# USB_Serial_Quad.net
KiCad netlist of a schematic drawn in Altium Designer
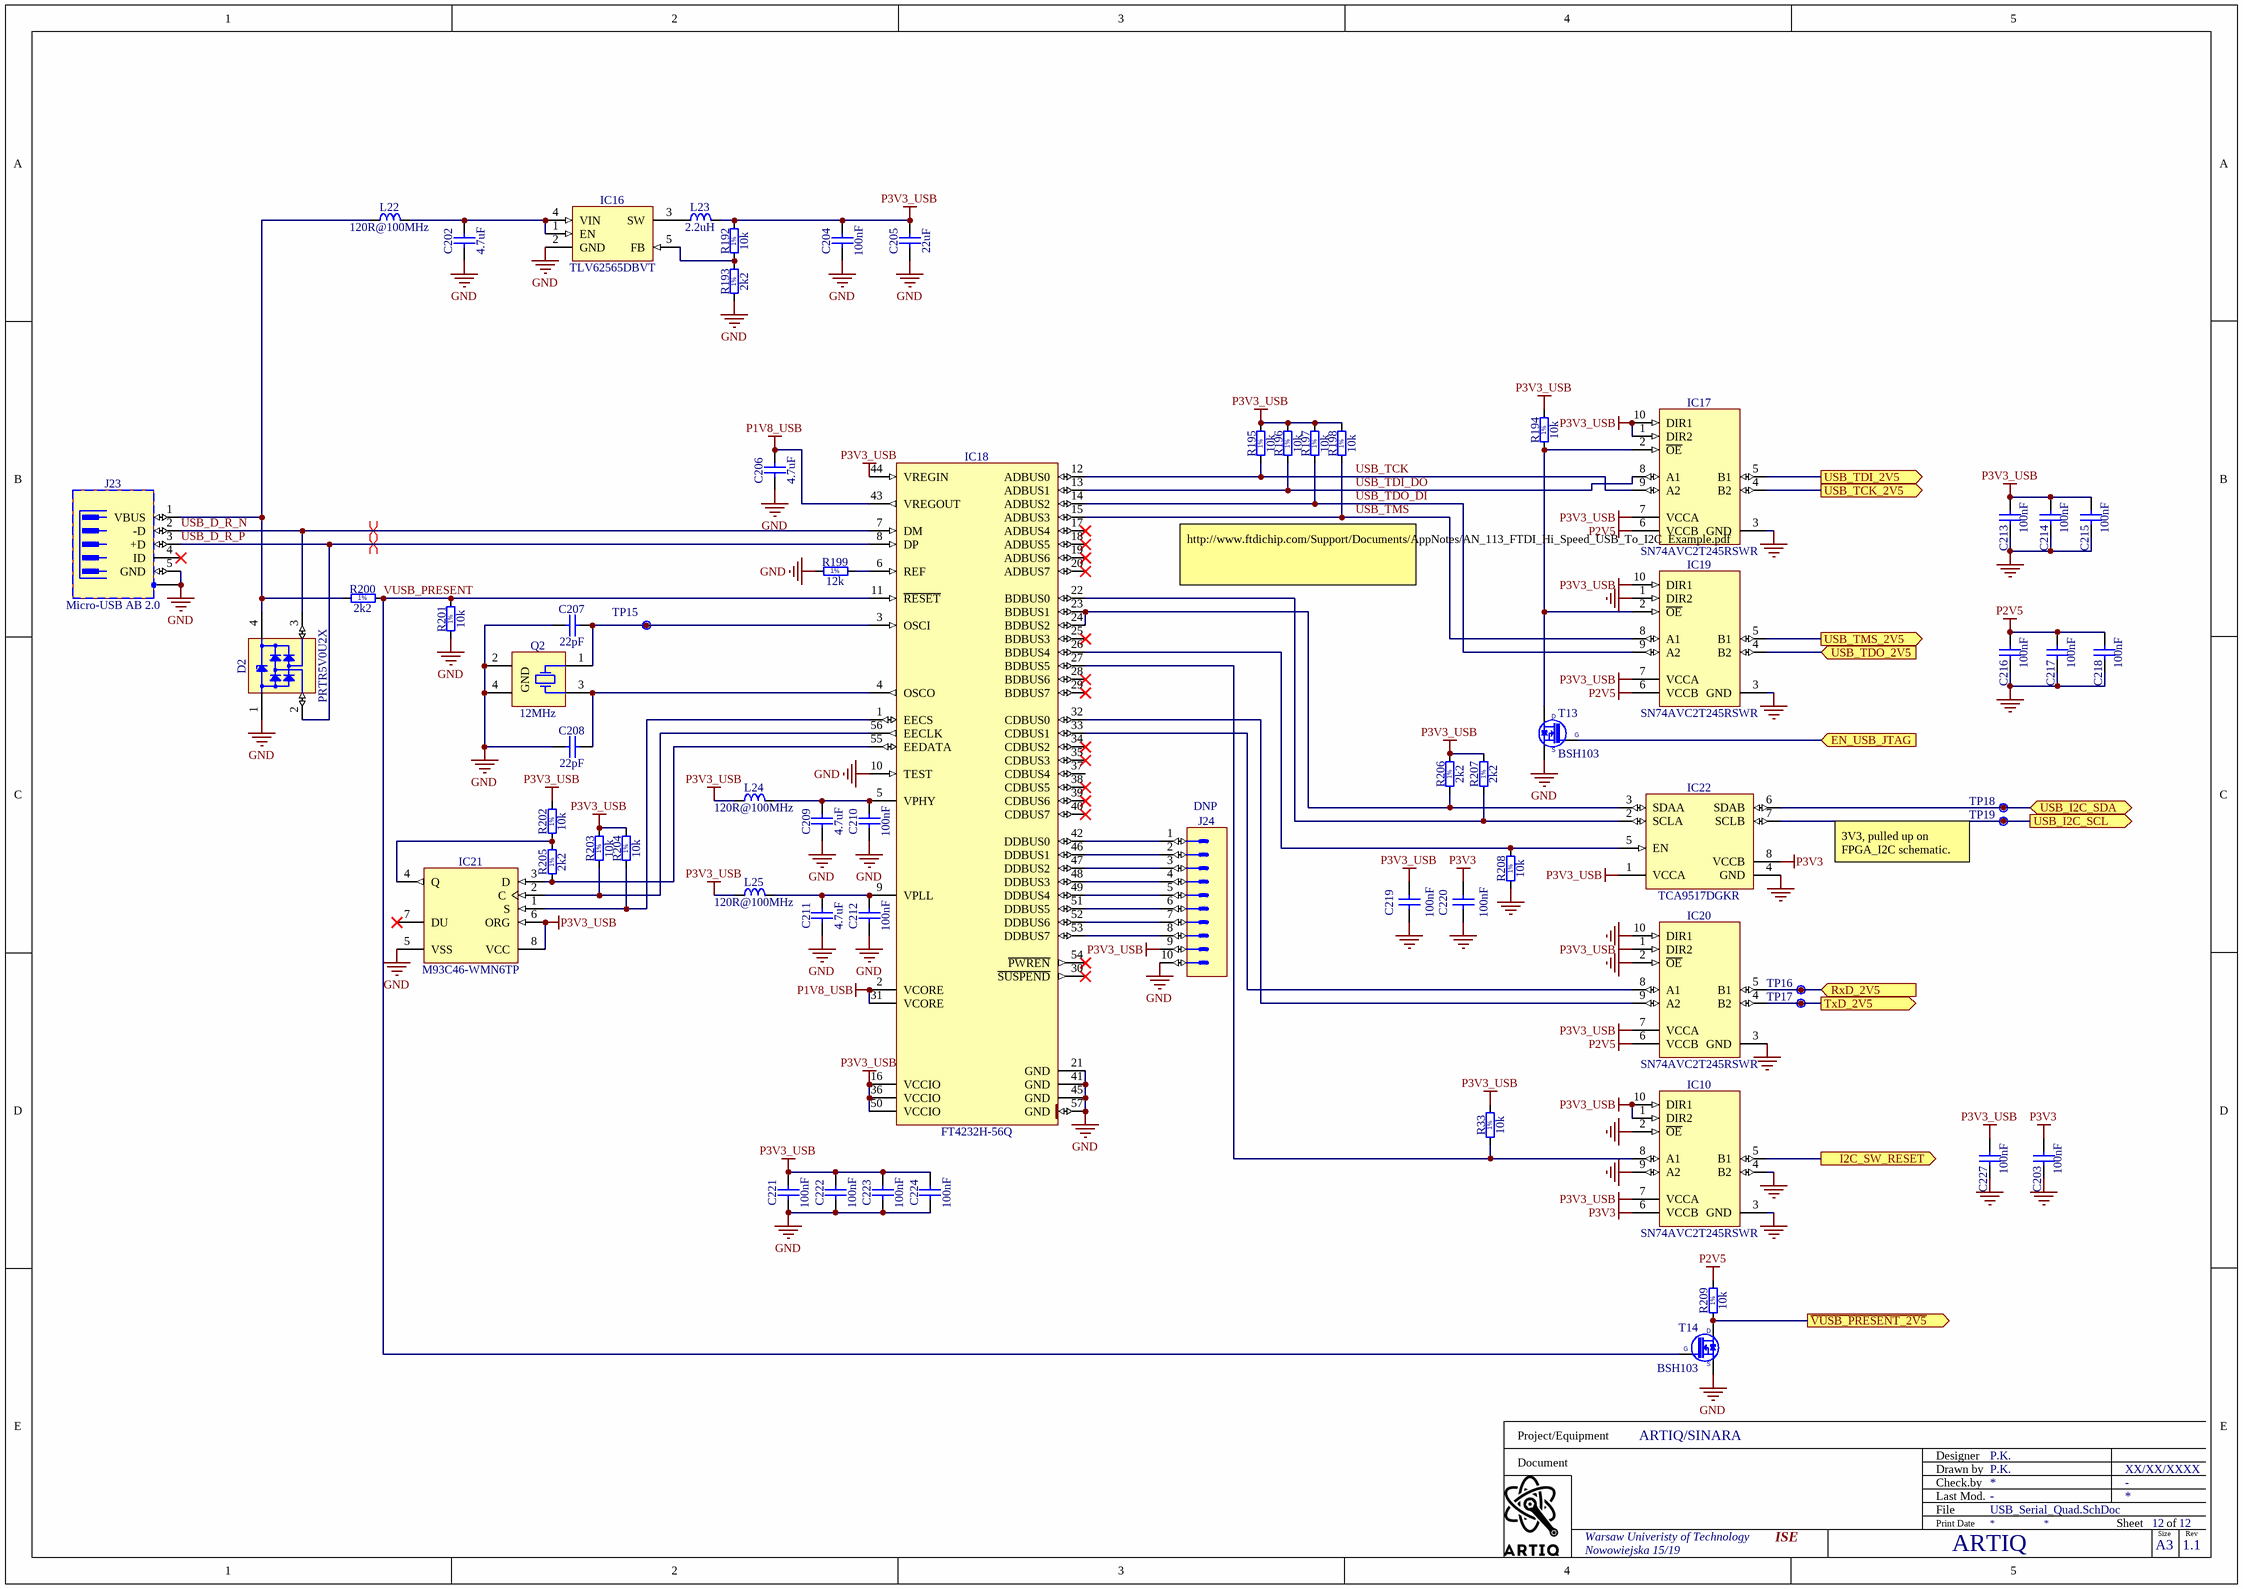
[diagram p0: USB_Serial_Quad.SchDoc]

(export (version "E")
  (design (tool "Eeschema 10.0.6"))
  (components
    (comp (ref "C202")
      (value "4.7uF")
      (footprint "CAPC2012X135N")
      (description "Non-polarised capacitor")
      (fields
        (field (name "PART NUMBER") "CC0805_4.7UF_10V_10%_X5R")
        (field (name "VOLTAGE") "10V")
        (field (name "AUTHOR") "CERN DEM JLC")
      )
      (libsource (lib "Capacitors") (part "Capacitor - non polarized"))
    )
    (comp (ref "C203")
      (value "100nF")
      (footprint "CAPC0603X33N")
      (description "Non-polarised capacitor")
      (fields
        (field (name "PART NUMBER") "CC0201_100NF_6.3V_10%_X5R")
        (field (name "VOLTAGE") "6.3V")
        (field (name "AUTHOR") "CERN DEM JLC")
      )
      (libsource (lib "Capacitors") (part "Capacitor - non polarized"))
    )
    (comp (ref "C204")
      (value "100nF")
      (footprint "CAPC0603X33N")
      (description "Non-polarised capacitor")
      (fields
        (field (name "PART NUMBER") "CC0201_100NF_6.3V_10%_X5R")
        (field (name "VOLTAGE") "6.3V")
        (field (name "AUTHOR") "CERN DEM JLC")
      )
      (libsource (lib "Capacitors") (part "Capacitor - non polarized"))
    )
    (comp (ref "C205")
      (value "22uF")
      (footprint "CAPC1709X100N")
      (description "Non-polarised capacitor")
      (fields
        (field (name "PART NUMBER") "CC0603_22UF_6.3V_20%_X5R")
        (field (name "VOLTAGE") "6.3V")
        (field (name "AUTHOR") "CERN DEM JLC")
      )
      (libsource (lib "Capacitors") (part "Capacitor - non polarized"))
    )
    (comp (ref "C206")
      (value "4.7uF")
      (footprint "CAPC2012X135N")
      (description "Non-polarised capacitor")
      (fields
        (field (name "PART NUMBER") "CC0805_4.7UF_10V_10%_X5R")
        (field (name "VOLTAGE") "10V")
        (field (name "AUTHOR") "CERN DEM JLC")
      )
      (libsource (lib "Capacitors") (part "Capacitor - non polarized"))
    )
    (comp (ref "C207")
      (value "22pF")
      (footprint "CAPC1005X55N")
      (description "Non-polarised capacitor")
      (fields
        (field (name "PART NUMBER") "CC0402_22PF_50V_5%_C0G")
        (field (name "VOLTAGE") "50V")
        (field (name "AUTHOR") "CERN DEM JLC")
      )
      (libsource (lib "Capacitors") (part "Capacitor - non polarized"))
    )
    (comp (ref "C208")
      (value "22pF")
      (footprint "CAPC1005X55N")
      (description "Non-polarised capacitor")
      (fields
        (field (name "PART NUMBER") "CC0402_22PF_50V_5%_C0G")
        (field (name "VOLTAGE") "50V")
        (field (name "AUTHOR") "CERN DEM JLC")
      )
      (libsource (lib "Capacitors") (part "Capacitor - non polarized"))
    )
    (comp (ref "C209")
      (value "4.7uF")
      (footprint "CAPC2012X135N")
      (description "Non-polarised capacitor")
      (fields
        (field (name "PART NUMBER") "CC0805_4.7UF_10V_10%_X5R")
        (field (name "VOLTAGE") "10V")
        (field (name "AUTHOR") "CERN DEM JLC")
      )
      (libsource (lib "Capacitors") (part "Capacitor - non polarized"))
    )
    (comp (ref "C210")
      (value "100nF")
      (footprint "CAPC0603X33N")
      (description "Non-polarised capacitor")
      (fields
        (field (name "PART NUMBER") "CC0201_100NF_6.3V_10%_X5R")
        (field (name "VOLTAGE") "6.3V")
        (field (name "AUTHOR") "CERN DEM JLC")
      )
      (libsource (lib "Capacitors") (part "Capacitor - non polarized"))
    )
    (comp (ref "C211")
      (value "4.7uF")
      (footprint "CAPC2012X135N")
      (description "Non-polarised capacitor")
      (fields
        (field (name "PART NUMBER") "CC0805_4.7UF_10V_10%_X5R")
        (field (name "VOLTAGE") "10V")
        (field (name "AUTHOR") "CERN DEM JLC")
      )
      (libsource (lib "Capacitors") (part "Capacitor - non polarized"))
    )
    (comp (ref "C212")
      (value "100nF")
      (footprint "CAPC0603X33N")
      (description "Non-polarised capacitor")
      (fields
        (field (name "PART NUMBER") "CC0201_100NF_6.3V_10%_X5R")
        (field (name "VOLTAGE") "6.3V")
        (field (name "AUTHOR") "CERN DEM JLC")
      )
      (libsource (lib "Capacitors") (part "Capacitor - non polarized"))
    )
    (comp (ref "C213")
      (value "100nF")
      (footprint "CAPC0603X33N")
      (description "Non-polarised capacitor")
      (fields
        (field (name "PART NUMBER") "CC0201_100NF_6.3V_10%_X5R")
        (field (name "VOLTAGE") "6.3V")
        (field (name "AUTHOR") "CERN DEM JLC")
      )
      (libsource (lib "Capacitors") (part "Capacitor - non polarized"))
    )
    (comp (ref "C214")
      (value "100nF")
      (footprint "CAPC0603X33N")
      (description "Non-polarised capacitor")
      (fields
        (field (name "PART NUMBER") "CC0201_100NF_6.3V_10%_X5R")
        (field (name "VOLTAGE") "6.3V")
        (field (name "AUTHOR") "CERN DEM JLC")
      )
      (libsource (lib "Capacitors") (part "Capacitor - non polarized"))
    )
    (comp (ref "C215")
      (value "100nF")
      (footprint "CAPC0603X33N")
      (description "Non-polarised capacitor")
      (fields
        (field (name "PART NUMBER") "CC0201_100NF_6.3V_10%_X5R")
        (field (name "VOLTAGE") "6.3V")
        (field (name "AUTHOR") "CERN DEM JLC")
      )
      (libsource (lib "Capacitors") (part "Capacitor - non polarized"))
    )
    (comp (ref "C216")
      (value "100nF")
      (footprint "CAPC0603X33N")
      (description "Non-polarised capacitor")
      (fields
        (field (name "PART NUMBER") "CC0201_100NF_6.3V_10%_X5R")
        (field (name "VOLTAGE") "6.3V")
        (field (name "AUTHOR") "CERN DEM JLC")
      )
      (libsource (lib "Capacitors") (part "Capacitor - non polarized"))
    )
    (comp (ref "C217")
      (value "100nF")
      (footprint "CAPC0603X33N")
      (description "Non-polarised capacitor")
      (fields
        (field (name "PART NUMBER") "CC0201_100NF_6.3V_10%_X5R")
        (field (name "VOLTAGE") "6.3V")
        (field (name "AUTHOR") "CERN DEM JLC")
      )
      (libsource (lib "Capacitors") (part "Capacitor - non polarized"))
    )
    (comp (ref "C218")
      (value "100nF")
      (footprint "CAPC0603X33N")
      (description "Non-polarised capacitor")
      (fields
        (field (name "PART NUMBER") "CC0201_100NF_6.3V_10%_X5R")
        (field (name "VOLTAGE") "6.3V")
        (field (name "AUTHOR") "CERN DEM JLC")
      )
      (libsource (lib "Capacitors") (part "Capacitor - non polarized"))
    )
    (comp (ref "C219")
      (value "100nF")
      (footprint "CAPC0603X33N")
      (description "Non-polarised capacitor")
      (fields
        (field (name "PART NUMBER") "CC0201_100NF_6.3V_10%_X5R")
        (field (name "VOLTAGE") "6.3V")
        (field (name "AUTHOR") "CERN DEM JLC")
      )
      (libsource (lib "Capacitors") (part "Capacitor - non polarized"))
    )
    (comp (ref "C220")
      (value "100nF")
      (footprint "CAPC0603X33N")
      (description "Non-polarised capacitor")
      (fields
        (field (name "PART NUMBER") "CC0201_100NF_6.3V_10%_X5R")
        (field (name "VOLTAGE") "6.3V")
        (field (name "AUTHOR") "CERN DEM JLC")
      )
      (libsource (lib "Capacitors") (part "Capacitor - non polarized"))
    )
    (comp (ref "C221")
      (value "100nF")
      (footprint "CAPC0603X33N")
      (description "Non-polarised capacitor")
      (fields
        (field (name "PART NUMBER") "CC0201_100NF_6.3V_10%_X5R")
        (field (name "VOLTAGE") "6.3V")
        (field (name "AUTHOR") "CERN DEM JLC")
      )
      (libsource (lib "Capacitors") (part "Capacitor - non polarized"))
    )
    (comp (ref "C222")
      (value "100nF")
      (footprint "CAPC0603X33N")
      (description "Non-polarised capacitor")
      (fields
        (field (name "PART NUMBER") "CC0201_100NF_6.3V_10%_X5R")
        (field (name "VOLTAGE") "6.3V")
        (field (name "AUTHOR") "CERN DEM JLC")
      )
      (libsource (lib "Capacitors") (part "Capacitor - non polarized"))
    )
    (comp (ref "C223")
      (value "100nF")
      (footprint "CAPC0603X33N")
      (description "Non-polarised capacitor")
      (fields
        (field (name "PART NUMBER") "CC0201_100NF_6.3V_10%_X5R")
        (field (name "VOLTAGE") "6.3V")
        (field (name "AUTHOR") "CERN DEM JLC")
      )
      (libsource (lib "Capacitors") (part "Capacitor - non polarized"))
    )
    (comp (ref "C224")
      (value "100nF")
      (footprint "CAPC0603X33N")
      (description "Non-polarised capacitor")
      (fields
        (field (name "PART NUMBER") "CC0201_100NF_6.3V_10%_X5R")
        (field (name "VOLTAGE") "6.3V")
        (field (name "AUTHOR") "CERN DEM JLC")
      )
      (libsource (lib "Capacitors") (part "Capacitor - non polarized"))
    )
    (comp (ref "C227")
      (value "100nF")
      (footprint "CAPC0603X33N")
      (description "Non-polarised capacitor")
      (fields
        (field (name "PART NUMBER") "CC0201_100NF_6.3V_10%_X5R")
        (field (name "VOLTAGE") "6.3V")
        (field (name "AUTHOR") "CERN DEM JLC")
      )
      (libsource (lib "Capacitors") (part "Capacitor - non polarized"))
    )
    (comp (ref "D2")
      (value "PRTR5V0U2X")
      (footprint "SOT190P230X110-4N")
      (description "Ultra Low Capacitance Double Rail-to-Rail ESD Protection Diode")
      (fields
        (field (name "VOLTAGE") "5.5V")
        (field (name "MANUFACTURER") "NXP SEMICONDUCTORS")
        (field (name "AUTHOR") "CERN DEM JLC")
      )
      (libsource (lib "ICs And Semiconductors") (part "PRTR5V0U2X"))
    )
    (comp (ref "IC10")
      (value "SN74AVC2T245RSWR")
      (footprint "QFN40P140X180X55-10N")
      (description "Dual-Bit Dual-Supply Bus Transceiver With Configurable Voltage Translation and 3-State Outputs")
      (fields (field (name "MANUFACTURER") "TEXAS INSTRUMENTS") (field (name "AUTHOR") "CERN DEM JLC"))
      (libsource (lib "ICs And Semiconductors") (part "742T245"))
    )
    (comp (ref "IC16")
      (value "TLV62565DBVT")
      (footprint "SOT95P280X145-5N")
      (description "1.5A High Efficiency Step-Down Converter, Adjustable Output Voltage")
      (fields (field (name "MANUFACTURER") "TEXAS INSTRUMENTS") (field (name "AUTHOR") "CERN DEM JMW"))
      (libsource (lib "ICs And Semiconductors") (part "TLV62565"))
    )
    (comp (ref "IC17")
      (value "SN74AVC2T245RSWR")
      (footprint "QFN40P140X180X55-10N")
      (description "Dual-Bit Dual-Supply Bus Transceiver With Configurable Voltage Translation and 3-State Outputs")
      (fields (field (name "MANUFACTURER") "TEXAS INSTRUMENTS") (field (name "AUTHOR") "CERN DEM JLC"))
      (libsource (lib "ICs And Semiconductors") (part "742T245"))
    )
    (comp (ref "IC18")
      (value "FT4232H-56Q")
      (footprint "QFN50P800X800X100-57N-S620")
      (description "Quad High Speed USB to Multipurpose UART/MPSSE IC")
      (fields
        (field (name "MANUFACTURER") "FUTURE TECHNOLOGY DEVICES INTERNATIONAL (FTDI)")
        (field (name "AUTHOR") "CERN DEM JLC")
      )
      (libsource (lib "ICs And Semiconductors") (part "FT4232H-56Q"))
    )
    (comp (ref "IC19")
      (value "SN74AVC2T245RSWR")
      (footprint "QFN40P140X180X55-10N")
      (description "Dual-Bit Dual-Supply Bus Transceiver With Configurable Voltage Translation and 3-State Outputs")
      (fields (field (name "MANUFACTURER") "TEXAS INSTRUMENTS") (field (name "AUTHOR") "CERN DEM JLC"))
      (libsource (lib "ICs And Semiconductors") (part "742T245"))
    )
    (comp (ref "IC20")
      (value "SN74AVC2T245RSWR")
      (footprint "QFN40P140X180X55-10N")
      (description "Dual-Bit Dual-Supply Bus Transceiver With Configurable Voltage Translation and 3-State Outputs")
      (fields (field (name "MANUFACTURER") "TEXAS INSTRUMENTS") (field (name "AUTHOR") "CERN DEM JLC"))
      (libsource (lib "ICs And Semiconductors") (part "742T245"))
    )
    (comp (ref "IC21")
      (value "M93C46-WMN6TP")
      (footprint "SOIC127P600X175-8N")
      (description "2.5 to 5.5 V, 1Kb (128x8) Serial Microwire Bus EEPROM")
      (fields (field (name "MANUFACTURER") "ST MICROELECTRONICS") (field (name "AUTHOR") "CERN DEM JLC"))
      (libsource (lib "ICs And Semiconductors") (part "M93C46-WMN6TP"))
    )
    (comp (ref "IC22")
      (value "TCA9517DGKR")
      (footprint "SOP65P490X110-8N")
      (description "Level-Translating I2C Bus Repeater")
      (fields (field (name "MANUFACTURER") "TEXAS INSTRUMENTS") (field (name "AUTHOR") "CERN DEM JLC"))
      (libsource (lib "ICs And Semiconductors") (part "TCA9517"))
    )
    (comp (ref "J23")
      (value "Micro-USB AB 2.0")
      (footprint "HIROSE_ZX62RD-AB-5P8")
      (description "5 Pin + 1 Shield USB Receptacle")
      (fields
        (field (name "PART NUMBER") "HIROSE_ZX62RD-AB-5P8")
        (field (name "MANUFACTURER") "HIROSE (HRS)")
        (field (name "AUTHOR") "CERN DEM JLC")
      )
      (libsource (lib "Connectors") (part "Connector USB 5 Pin + 1Shield"))
    )
    (comp (ref "J24")
      (value "Header 10")
      (footprint "SAMTEC_TSW-105-07-L-D-LL")
      (description "Connector 10 Male")
      (fields
        (field (name "PART NUMBER") "SAMTEC_TSW-105-07-L-D-LL")
        (field (name "MANUFACTURER") "SAMTEC")
        (field (name "AUTHOR") "CERN DEM JLC")
      )
      (libsource (lib "Connectors") (part "Connector 10 Male"))
    )
    (comp (ref "L22")
      (value "120R@100MHz")
      (footprint "INDC1608X65N")
      (description "Inductor")
      (fields
        (field (name "PART NUMBER") "IND0603_MURATA_BLM18SG121TN1D")
        (field (name "POWER") "3A")
        (field (name "AUTHOR") "CERN DEM JLC")
      )
      (libsource (lib "Inductors & Transformers") (part "Inductor"))
    )
    (comp (ref "L23")
      (value "2.2uH")
      (footprint "IND_WURTH_WE-PMCI_0806LR")
      (description "Inductor")
      (fields
        (field (name "PART NUMBER") "IND_2.2UH_20%_WURTH_WE-PMCI_74479276222C")
        (field (name "POWER") "1.1A")
        (field (name "AUTHOR") "CERN DEM JLC")
      )
      (libsource (lib "Inductors & Transformers") (part "Inductor"))
    )
    (comp (ref "L24")
      (value "120R@100MHz")
      (footprint "INDC1608X65N")
      (description "Inductor")
      (fields
        (field (name "PART NUMBER") "IND0603_MURATA_BLM18SG121TN1D")
        (field (name "POWER") "3A")
        (field (name "AUTHOR") "CERN DEM JLC")
      )
      (libsource (lib "Inductors & Transformers") (part "Inductor"))
    )
    (comp (ref "L25")
      (value "120R@100MHz")
      (footprint "INDC1608X65N")
      (description "Inductor")
      (fields
        (field (name "PART NUMBER") "IND0603_MURATA_BLM18SG121TN1D")
        (field (name "POWER") "3A")
        (field (name "AUTHOR") "CERN DEM JLC")
      )
      (libsource (lib "Inductors & Transformers") (part "Inductor"))
    )
    (comp (ref "Q2")
      (value "12MHz")
      (footprint "XTAL_TXC_7M")
      (description "Crystal 4 pins 1=XTAL Control 2=GND3=XTAL 4=GND")
      (fields
        (field (name "PART NUMBER") "XTAL_12MHZ_TXC_7M-12.000MAAJ-T")
        (field (name "MANUFACTURER") "TXC CORPORATION")
        (field (name "AUTHOR") "CERN DEM JLC")
      )
      (libsource (lib "ICs And Semiconductors") (part "Quartz Crystal 1X 2GND 3X 4GND"))
    )
    (comp (ref "R33")
      (value "10k")
      (footprint "RESC1005X40N")
      (description "Resistor - 1%")
      (fields
        (field (name "PART NUMBER") "R0402_10K_1%_0.0625W_100PPM")
        (field (name "POWER") "0.0625W")
        (field (name "AUTHOR") "CERN DEM JLC")
      )
      (libsource (lib "Resistors") (part "Resistor - 1%"))
    )
    (comp (ref "R192")
      (value "10k")
      (footprint "RESC1005X40N")
      (description "Resistor - 1%")
      (fields
        (field (name "PART NUMBER") "R0402_10K_1%_0.0625W_100PPM")
        (field (name "POWER") "0.0625W")
        (field (name "AUTHOR") "CERN DEM JLC")
      )
      (libsource (lib "Resistors") (part "Resistor - 1%"))
    )
    (comp (ref "R193")
      (value "2k2")
      (footprint "RESC1005X40N")
      (description "Resistor - 1%")
      (fields
        (field (name "PART NUMBER") "R0402_2K2_1%_0.0625W_100PPM")
        (field (name "POWER") "0.0625W")
        (field (name "AUTHOR") "CERN DEM JLC")
      )
      (libsource (lib "Resistors") (part "Resistor - 1%"))
    )
    (comp (ref "R194")
      (value "10k")
      (footprint "RESC1005X40N")
      (description "Resistor - 1%")
      (fields
        (field (name "PART NUMBER") "R0402_10K_1%_0.0625W_100PPM")
        (field (name "POWER") "0.0625W")
        (field (name "AUTHOR") "CERN DEM JLC")
      )
      (libsource (lib "Resistors") (part "Resistor - 1%"))
    )
    (comp (ref "R195")
      (value "10k")
      (footprint "RESC1005X40N")
      (description "Resistor - 1%")
      (fields
        (field (name "PART NUMBER") "R0402_10K_1%_0.0625W_100PPM")
        (field (name "POWER") "0.0625W")
        (field (name "AUTHOR") "CERN DEM JLC")
      )
      (libsource (lib "Resistors") (part "Resistor - 1%"))
    )
    (comp (ref "R196")
      (value "10k")
      (footprint "RESC1005X40N")
      (description "Resistor - 1%")
      (fields
        (field (name "PART NUMBER") "R0402_10K_1%_0.0625W_100PPM")
        (field (name "POWER") "0.0625W")
        (field (name "AUTHOR") "CERN DEM JLC")
      )
      (libsource (lib "Resistors") (part "Resistor - 1%"))
    )
    (comp (ref "R197")
      (value "10k")
      (footprint "RESC1005X40N")
      (description "Resistor - 1%")
      (fields
        (field (name "PART NUMBER") "R0402_10K_1%_0.0625W_100PPM")
        (field (name "POWER") "0.0625W")
        (field (name "AUTHOR") "CERN DEM JLC")
      )
      (libsource (lib "Resistors") (part "Resistor - 1%"))
    )
    (comp (ref "R198")
      (value "10k")
      (footprint "RESC1005X40N")
      (description "Resistor - 1%")
      (fields
        (field (name "PART NUMBER") "R0402_10K_1%_0.0625W_100PPM")
        (field (name "POWER") "0.0625W")
        (field (name "AUTHOR") "CERN DEM JLC")
      )
      (libsource (lib "Resistors") (part "Resistor - 1%"))
    )
    (comp (ref "R199")
      (value "12k")
      (footprint "RESC1005X40N")
      (description "Resistor - 1%")
      (fields
        (field (name "PART NUMBER") "R0402_12K_1%_0.0625W_100PPM")
        (field (name "POWER") "0.0625W")
        (field (name "AUTHOR") "CERN DEM JLC")
      )
      (libsource (lib "Resistors") (part "Resistor - 1%"))
    )
    (comp (ref "R200")
      (value "2k2")
      (footprint "RESC1005X40N")
      (description "Resistor - 1%")
      (fields
        (field (name "PART NUMBER") "R0402_2K2_1%_0.0625W_100PPM")
        (field (name "POWER") "0.0625W")
        (field (name "AUTHOR") "CERN DEM JLC")
      )
      (libsource (lib "Resistors") (part "Resistor - 1%"))
    )
    (comp (ref "R201")
      (value "10k")
      (footprint "RESC1005X40N")
      (description "Resistor - 1%")
      (fields
        (field (name "PART NUMBER") "R0402_10K_1%_0.0625W_100PPM")
        (field (name "POWER") "0.0625W")
        (field (name "AUTHOR") "CERN DEM JLC")
      )
      (libsource (lib "Resistors") (part "Resistor - 1%"))
    )
    (comp (ref "R202")
      (value "10k")
      (footprint "RESC1005X40N")
      (description "Resistor - 1%")
      (fields
        (field (name "PART NUMBER") "R0402_10K_1%_0.0625W_100PPM")
        (field (name "POWER") "0.0625W")
        (field (name "AUTHOR") "CERN DEM JLC")
      )
      (libsource (lib "Resistors") (part "Resistor - 1%"))
    )
    (comp (ref "R203")
      (value "10k")
      (footprint "RESC1005X40N")
      (description "Resistor - 1%")
      (fields
        (field (name "PART NUMBER") "R0402_10K_1%_0.0625W_100PPM")
        (field (name "POWER") "0.0625W")
        (field (name "AUTHOR") "CERN DEM JLC")
      )
      (libsource (lib "Resistors") (part "Resistor - 1%"))
    )
    (comp (ref "R204")
      (value "10k")
      (footprint "RESC1005X40N")
      (description "Resistor - 1%")
      (fields
        (field (name "PART NUMBER") "R0402_10K_1%_0.0625W_100PPM")
        (field (name "POWER") "0.0625W")
        (field (name "AUTHOR") "CERN DEM JLC")
      )
      (libsource (lib "Resistors") (part "Resistor - 1%"))
    )
    (comp (ref "R205")
      (value "2k2")
      (footprint "RESC1005X40N")
      (description "Resistor - 1%")
      (fields
        (field (name "PART NUMBER") "R0402_2K2_1%_0.0625W_100PPM")
        (field (name "POWER") "0.0625W")
        (field (name "AUTHOR") "CERN DEM JLC")
      )
      (libsource (lib "Resistors") (part "Resistor - 1%"))
    )
    (comp (ref "R206")
      (value "2k2")
      (footprint "RESC1005X40N")
      (description "Resistor - 1%")
      (fields
        (field (name "PART NUMBER") "R0402_2K2_1%_0.0625W_100PPM")
        (field (name "POWER") "0.0625W")
        (field (name "AUTHOR") "CERN DEM JLC")
      )
      (libsource (lib "Resistors") (part "Resistor - 1%"))
    )
    (comp (ref "R207")
      (value "2k2")
      (footprint "RESC1005X40N")
      (description "Resistor - 1%")
      (fields
        (field (name "PART NUMBER") "R0402_2K2_1%_0.0625W_100PPM")
        (field (name "POWER") "0.0625W")
        (field (name "AUTHOR") "CERN DEM JLC")
      )
      (libsource (lib "Resistors") (part "Resistor - 1%"))
    )
    (comp (ref "R208")
      (value "10k")
      (footprint "RESC1005X40N")
      (description "Resistor - 1%")
      (fields
        (field (name "PART NUMBER") "R0402_10K_1%_0.0625W_100PPM")
        (field (name "POWER") "0.0625W")
        (field (name "AUTHOR") "CERN DEM JLC")
      )
      (libsource (lib "Resistors") (part "Resistor - 1%"))
    )
    (comp (ref "R209")
      (value "10k")
      (footprint "RESC1005X40N")
      (description "Resistor - 1%")
      (fields
        (field (name "PART NUMBER") "R0402_10K_1%_0.0625W_100PPM")
        (field (name "POWER") "0.0625W")
        (field (name "AUTHOR") "CERN DEM JLC")
      )
      (libsource (lib "Resistors") (part "Resistor - 1%"))
    )
    (comp (ref "T13")
      (value "BSH103")
      (footprint "SOT95P230X110-3N")
      (description "N-CHANNEL MOSFET WITH DIODE")
      (fields (field (name "MANUFACTURER") "NEXPERIA") (field (name "AUTHOR") "CERN DEM JLC"))
      (libsource (lib "") (part "N-MOSFET-D 1G 2S 3D_1"))
    )
    (comp (ref "T14")
      (value "BSH103")
      (footprint "SOT95P230X110-3N")
      (description "N-CHANNEL MOSFET WITH DIODE")
      (fields (field (name "MANUFACTURER") "NEXPERIA") (field (name "AUTHOR") "CERN DEM JLC"))
      (libsource (lib "ICs And Semiconductors") (part "N-MOSFET-D 1G 2S 3D"))
    )
    (comp (ref "TP15")
      (value "Q2")
      (footprint "TPS127")
      (description "Test Point")
      (fields (field (name "PART NUMBER") "SMD_PAD_1.27X1.27MM") (field (name "AUTHOR") "CERN DEM JLC"))
      (libsource (lib "Eletro-mechanical") (part "Test Point"))
    )
    (comp (ref "TP16")
      (value "RxD")
      (footprint "TPS127")
      (description "Test Point")
      (fields (field (name "PART NUMBER") "SMD_PAD_1.27X1.27MM") (field (name "AUTHOR") "CERN DEM JLC"))
      (libsource (lib "Eletro-mechanical") (part "Test Point"))
    )
    (comp (ref "TP17")
      (value "TxD")
      (footprint "TPS127")
      (description "Test Point")
      (fields (field (name "PART NUMBER") "SMD_PAD_1.27X1.27MM") (field (name "AUTHOR") "CERN DEM JLC"))
      (libsource (lib "Eletro-mechanical") (part "Test Point"))
    )
    (comp (ref "TP18")
      (value "USB I2C SDA")
      (footprint "TPS127")
      (description "Test Point")
      (fields (field (name "PART NUMBER") "SMD_PAD_1.27X1.27MM") (field (name "AUTHOR") "CERN DEM JLC"))
      (libsource (lib "Eletro-mechanical") (part "Test Point"))
    )
    (comp (ref "TP19")
      (value "USB I2C SCL")
      (footprint "TPS127")
      (description "Test Point")
      (fields (field (name "PART NUMBER") "SMD_PAD_1.27X1.27MM") (field (name "AUTHOR") "CERN DEM JLC"))
      (libsource (lib "Eletro-mechanical") (part "Test Point"))
    )
  )
  (nets
    (net (code "1") (name "/EN_USB_JTAG") (class "Default")
      (node (ref "T13") (pin "1") (pinfunction "G_1") (pintype "passive"))
    )
    (net (code "2") (name "/I2C_SW_RESET") (class "Default")
      (node (ref "IC10") (pin "5") (pinfunction "B1_5") (pintype "bidirectional"))
    )
    (net (code "3") (name "/RxD_2V5") (class "Default")
      (node (ref "IC20") (pin "5") (pinfunction "B1_5") (pintype "bidirectional"))
      (node (ref "TP16") (pin "1") (pinfunction "1_1") (pintype "bidirectional"))
    )
    (net (code "4") (name "/TxD_2V5") (class "Default")
      (node (ref "IC20") (pin "4") (pinfunction "B2_4") (pintype "bidirectional"))
      (node (ref "TP17") (pin "1") (pinfunction "1_1") (pintype "bidirectional"))
    )
    (net (code "5") (name "/USB_D_R_N") (class "Default")
      (node (ref "D2") (pin "3") (pinfunction "I/O2_3") (pintype "bidirectional"))
      (node (ref "IC18") (pin "7") (pinfunction "DM_7") (pintype "input"))
      (node (ref "J23") (pin "2") (pinfunction "-D_2") (pintype "bidirectional"))
    )
    (net (code "6") (name "/USB_D_R_P") (class "Default")
      (node (ref "D2") (pin "2") (pinfunction "I/O1_2") (pintype "bidirectional"))
      (node (ref "IC18") (pin "8") (pinfunction "DP_8") (pintype "input"))
      (node (ref "J23") (pin "3") (pinfunction "+D_3") (pintype "bidirectional"))
    )
    (net (code "7") (name "/USB_I2C_SCL") (class "Default")
      (node (ref "IC22") (pin "7") (pinfunction "SCLB_7") (pintype "bidirectional"))
      (node (ref "TP19") (pin "1") (pinfunction "1_1") (pintype "bidirectional"))
    )
    (net (code "8") (name "/USB_I2C_SDA") (class "Default")
      (node (ref "IC22") (pin "6") (pinfunction "SDAB_6") (pintype "bidirectional"))
      (node (ref "TP18") (pin "1") (pinfunction "1_1") (pintype "bidirectional"))
    )
    (net (code "9") (name "/USB_TCK") (class "Default")
      (node (ref "IC17") (pin "9") (pinfunction "A2_9") (pintype "bidirectional"))
      (node (ref "IC18") (pin "12") (pinfunction "ADBUS0_12") (pintype "bidirectional"))
      (node (ref "R195") (pin "1") (pinfunction "1_1") (pintype "passive"))
    )
    (net (code "10") (name "/USB_TCK_2V5") (class "Default")
      (node (ref "IC17") (pin "4") (pinfunction "B2_4") (pintype "bidirectional"))
    )
    (net (code "11") (name "/USB_TDI_2V5") (class "Default")
      (node (ref "IC17") (pin "5") (pinfunction "B1_5") (pintype "bidirectional"))
    )
    (net (code "12") (name "/USB_TDI_DO") (class "Default")
      (node (ref "IC17") (pin "8") (pinfunction "A1_8") (pintype "bidirectional"))
      (node (ref "IC18") (pin "13") (pinfunction "ADBUS1_13") (pintype "bidirectional"))
      (node (ref "R196") (pin "1") (pinfunction "1_1") (pintype "passive"))
    )
    (net (code "13") (name "/USB_TDO_2V5") (class "Default")
      (node (ref "IC19") (pin "4") (pinfunction "B2_4") (pintype "bidirectional"))
    )
    (net (code "14") (name "/USB_TDO_DI") (class "Default")
      (node (ref "IC18") (pin "14") (pinfunction "ADBUS2_14") (pintype "bidirectional"))
      (node (ref "IC19") (pin "9") (pinfunction "A2_9") (pintype "bidirectional"))
      (node (ref "R197") (pin "1") (pinfunction "1_1") (pintype "passive"))
    )
    (net (code "15") (name "/USB_TMS") (class "Default")
      (node (ref "IC18") (pin "15") (pinfunction "ADBUS3_15") (pintype "bidirectional"))
      (node (ref "IC19") (pin "8") (pinfunction "A1_8") (pintype "bidirectional"))
      (node (ref "R198") (pin "1") (pinfunction "1_1") (pintype "passive"))
    )
    (net (code "16") (name "/USB_TMS_2V5") (class "Default")
      (node (ref "IC19") (pin "5") (pinfunction "B1_5") (pintype "bidirectional"))
    )
    (net (code "17") (name "/VUSB_PRESENT") (class "Default")
      (node (ref "IC18") (pin "11") (pinfunction "~{RESET}_11") (pintype "input"))
      (node (ref "R200") (pin "2") (pinfunction "2_2") (pintype "passive"))
      (node (ref "R201") (pin "2") (pinfunction "2_2") (pintype "passive"))
      (node (ref "T14") (pin "1") (pinfunction "G_1") (pintype "passive"))
    )
    (net (code "18") (name "/VUSB_PRESENT_2V5") (class "Default")
      (node (ref "R209") (pin "1") (pinfunction "1_1") (pintype "passive"))
      (node (ref "T14") (pin "3") (pinfunction "D_3") (pintype "passive"))
    )
    (net (code "19") (name "GND") (class "Default")
      (node (ref "C202") (pin "1") (pinfunction "1_1") (pintype "passive"))
      (node (ref "C203") (pin "1") (pinfunction "1_1") (pintype "passive"))
      (node (ref "C204") (pin "1") (pinfunction "1_1") (pintype "passive"))
      (node (ref "C205") (pin "1") (pinfunction "1_1") (pintype "passive"))
      (node (ref "C206") (pin "1") (pinfunction "1_1") (pintype "passive"))
      (node (ref "C207") (pin "1") (pinfunction "1_1") (pintype "passive"))
      (node (ref "C208") (pin "1") (pinfunction "1_1") (pintype "passive"))
      (node (ref "C209") (pin "1") (pinfunction "1_1") (pintype "passive"))
      (node (ref "C210") (pin "1") (pinfunction "1_1") (pintype "passive"))
      (node (ref "C211") (pin "1") (pinfunction "1_1") (pintype "passive"))
      (node (ref "C212") (pin "1") (pinfunction "1_1") (pintype "passive"))
      (node (ref "C213") (pin "1") (pinfunction "1_1") (pintype "passive"))
      (node (ref "C214") (pin "1") (pinfunction "1_1") (pintype "passive"))
      (node (ref "C215") (pin "1") (pinfunction "1_1") (pintype "passive"))
      (node (ref "C216") (pin "1") (pinfunction "1_1") (pintype "passive"))
      (node (ref "C217") (pin "1") (pinfunction "1_1") (pintype "passive"))
      (node (ref "C218") (pin "1") (pinfunction "1_1") (pintype "passive"))
      (node (ref "C219") (pin "1") (pinfunction "1_1") (pintype "passive"))
      (node (ref "C220") (pin "1") (pinfunction "1_1") (pintype "passive"))
      (node (ref "C221") (pin "1") (pinfunction "1_1") (pintype "passive"))
      (node (ref "C222") (pin "1") (pinfunction "1_1") (pintype "passive"))
      (node (ref "C223") (pin "1") (pinfunction "1_1") (pintype "passive"))
      (node (ref "C224") (pin "1") (pinfunction "1_1") (pintype "passive"))
      (node (ref "C227") (pin "1") (pinfunction "1_1") (pintype "passive"))
      (node (ref "D2") (pin "1") (pinfunction "GND_1") (pintype "power_in"))
      (node (ref "IC10") (pin "2") (pinfunction "~{OE}_2") (pintype "input"))
      (node (ref "IC10") (pin "3") (pinfunction "GND_3") (pintype "power_in"))
      (node (ref "IC10") (pin "4") (pinfunction "B2_4") (pintype "bidirectional"))
      (node (ref "IC10") (pin "9") (pinfunction "A2_9") (pintype "bidirectional"))
      (node (ref "IC16") (pin "2") (pinfunction "GND_2") (pintype "power_in"))
      (node (ref "IC17") (pin "3") (pinfunction "GND_3") (pintype "power_in"))
      (node (ref "IC18") (pin "10") (pinfunction "TEST_10") (pintype "input"))
      (node (ref "IC18") (pin "21") (pinfunction "GND_21") (pintype "power_in"))
      (node (ref "IC18") (pin "41") (pinfunction "GND_41") (pintype "power_in"))
      (node (ref "IC18") (pin "45") (pinfunction "GND_45") (pintype "power_in"))
      (node (ref "IC18") (pin "57") (pinfunction "GND_57") (pintype "bidirectional"))
      (node (ref "IC19") (pin "1") (pinfunction "DIR2_1") (pintype "input"))
      (node (ref "IC19") (pin "3") (pinfunction "GND_3") (pintype "power_in"))
      (node (ref "IC20") (pin "10") (pinfunction "DIR1_10") (pintype "input"))
      (node (ref "IC20") (pin "2") (pinfunction "~{OE}_2") (pintype "input"))
      (node (ref "IC20") (pin "3") (pinfunction "GND_3") (pintype "power_in"))
      (node (ref "IC21") (pin "5") (pinfunction "VSS_5") (pintype "power_in"))
      (node (ref "IC22") (pin "4") (pinfunction "GND_4") (pintype "power_in"))
      (node (ref "J23") (pin "5") (pinfunction "GND_5") (pintype "bidirectional"))
      (node (ref "J23") (pin "6") (pinfunction "SH_6") (pintype "power_in"))
      (node (ref "J24") (pin "10") (pinfunction "10_10") (pintype "bidirectional"))
      (node (ref "Q2") (pin "2") (pinfunction "GND_2") (pintype "power_in"))
      (node (ref "Q2") (pin "4") (pinfunction "GND_4") (pintype "power_in"))
      (node (ref "R193") (pin "1") (pinfunction "1_1") (pintype "passive"))
      (node (ref "R199") (pin "1") (pinfunction "1_1") (pintype "passive"))
      (node (ref "R201") (pin "1") (pinfunction "1_1") (pintype "passive"))
      (node (ref "R208") (pin "1") (pinfunction "1_1") (pintype "passive"))
      (node (ref "T13") (pin "2") (pinfunction "S_2") (pintype "passive"))
      (node (ref "T14") (pin "2") (pinfunction "S_2") (pintype "passive"))
    )
    (net (code "20") (name "Net-(D2-VCC)") (class "Default")
      (node (ref "D2") (pin "4") (pinfunction "VCC_4") (pintype "power_in"))
      (node (ref "J23") (pin "1") (pinfunction "VBUS_1") (pintype "bidirectional"))
      (node (ref "L22") (pin "1") (pinfunction "1_1") (pintype "passive"))
      (node (ref "R200") (pin "1") (pinfunction "1_1") (pintype "passive"))
    )
    (net (code "21") (name "Net-(IC10-A1)") (class "Default")
      (node (ref "IC10") (pin "8") (pinfunction "A1_8") (pintype "bidirectional"))
      (node (ref "IC18") (pin "27") (pinfunction "BDBUS5_27") (pintype "bidirectional"))
      (node (ref "R33") (pin "1") (pinfunction "1_1") (pintype "passive"))
    )
    (net (code "22") (name "Net-(IC16-EN)") (class "Default")
      (node (ref "C202") (pin "2") (pinfunction "2_2") (pintype "passive"))
      (node (ref "IC16") (pin "1") (pinfunction "EN_1") (pintype "input"))
      (node (ref "IC16") (pin "4") (pinfunction "VIN_4") (pintype "input"))
      (node (ref "L22") (pin "2") (pinfunction "2_2") (pintype "passive"))
    )
    (net (code "23") (name "Net-(IC16-FB)") (class "Default")
      (node (ref "IC16") (pin "5") (pinfunction "FB_5") (pintype "input"))
      (node (ref "R192") (pin "1") (pinfunction "1_1") (pintype "passive"))
      (node (ref "R193") (pin "2") (pinfunction "2_2") (pintype "passive"))
    )
    (net (code "24") (name "Net-(IC16-SW)") (class "Default")
      (node (ref "IC16") (pin "3") (pinfunction "SW_3") (pintype "power_in"))
      (node (ref "L23") (pin "1") (pinfunction "1_1") (pintype "passive"))
    )
    (net (code "25") (name "Net-(IC17-~{OE})") (class "Default")
      (node (ref "IC17") (pin "2") (pinfunction "~{OE}_2") (pintype "input"))
      (node (ref "IC19") (pin "2") (pinfunction "~{OE}_2") (pintype "input"))
      (node (ref "R194") (pin "1") (pinfunction "1_1") (pintype "passive"))
      (node (ref "T13") (pin "3") (pinfunction "D_3") (pintype "passive"))
    )
    (net (code "26") (name "Net-(IC18-BDBUS0)") (class "Default")
      (node (ref "IC18") (pin "22") (pinfunction "BDBUS0_22") (pintype "bidirectional"))
      (node (ref "IC22") (pin "2") (pinfunction "SCLA_2") (pintype "bidirectional"))
      (node (ref "R207") (pin "1") (pinfunction "1_1") (pintype "passive"))
    )
    (net (code "27") (name "Net-(IC18-BDBUS1)") (class "Default")
      (node (ref "IC18") (pin "23") (pinfunction "BDBUS1_23") (pintype "bidirectional"))
      (node (ref "IC18") (pin "24") (pinfunction "BDBUS2_24") (pintype "bidirectional"))
      (node (ref "IC22") (pin "3") (pinfunction "SDAA_3") (pintype "bidirectional"))
      (node (ref "R206") (pin "1") (pinfunction "1_1") (pintype "passive"))
    )
    (net (code "28") (name "Net-(IC18-BDBUS4)") (class "Default")
      (node (ref "IC18") (pin "26") (pinfunction "BDBUS4_26") (pintype "bidirectional"))
      (node (ref "IC22") (pin "5") (pinfunction "EN_5") (pintype "input"))
      (node (ref "R208") (pin "2") (pinfunction "2_2") (pintype "passive"))
    )
    (net (code "29") (name "Net-(IC18-CDBUS0)") (class "Default")
      (node (ref "IC18") (pin "32") (pinfunction "CDBUS0_32") (pintype "bidirectional"))
      (node (ref "IC20") (pin "9") (pinfunction "A2_9") (pintype "bidirectional"))
    )
    (net (code "30") (name "Net-(IC18-CDBUS1)") (class "Default")
      (node (ref "IC18") (pin "33") (pinfunction "CDBUS1_33") (pintype "bidirectional"))
      (node (ref "IC20") (pin "8") (pinfunction "A1_8") (pintype "bidirectional"))
    )
    (net (code "31") (name "Net-(IC18-DDBUS0)") (class "Default")
      (node (ref "IC18") (pin "42") (pinfunction "DDBUS0_42") (pintype "bidirectional"))
      (node (ref "J24") (pin "1") (pinfunction "1_1") (pintype "bidirectional"))
    )
    (net (code "32") (name "Net-(IC18-DDBUS1)") (class "Default")
      (node (ref "IC18") (pin "46") (pinfunction "DDBUS1_46") (pintype "bidirectional"))
      (node (ref "J24") (pin "2") (pinfunction "2_2") (pintype "bidirectional"))
    )
    (net (code "33") (name "Net-(IC18-DDBUS2)") (class "Default")
      (node (ref "IC18") (pin "47") (pinfunction "DDBUS2_47") (pintype "bidirectional"))
      (node (ref "J24") (pin "3") (pinfunction "3_3") (pintype "bidirectional"))
    )
    (net (code "34") (name "Net-(IC18-DDBUS3)") (class "Default")
      (node (ref "IC18") (pin "48") (pinfunction "DDBUS3_48") (pintype "bidirectional"))
      (node (ref "J24") (pin "4") (pinfunction "4_4") (pintype "bidirectional"))
    )
    (net (code "35") (name "Net-(IC18-DDBUS4)") (class "Default")
      (node (ref "IC18") (pin "49") (pinfunction "DDBUS4_49") (pintype "bidirectional"))
      (node (ref "J24") (pin "5") (pinfunction "5_5") (pintype "bidirectional"))
    )
    (net (code "36") (name "Net-(IC18-DDBUS5)") (class "Default")
      (node (ref "IC18") (pin "51") (pinfunction "DDBUS5_51") (pintype "bidirectional"))
      (node (ref "J24") (pin "6") (pinfunction "6_6") (pintype "bidirectional"))
    )
    (net (code "37") (name "Net-(IC18-DDBUS6)") (class "Default")
      (node (ref "IC18") (pin "52") (pinfunction "DDBUS6_52") (pintype "bidirectional"))
      (node (ref "J24") (pin "7") (pinfunction "7_7") (pintype "bidirectional"))
    )
    (net (code "38") (name "Net-(IC18-DDBUS7)") (class "Default")
      (node (ref "IC18") (pin "53") (pinfunction "DDBUS7_53") (pintype "bidirectional"))
      (node (ref "J24") (pin "8") (pinfunction "8_8") (pintype "bidirectional"))
    )
    (net (code "39") (name "Net-(IC18-EECLK)") (class "Default")
      (node (ref "IC18") (pin "56") (pinfunction "EECLK_56") (pintype "output"))
      (node (ref "IC21") (pin "2") (pinfunction "C_2") (pintype "input"))
      (node (ref "R203") (pin "1") (pinfunction "1_1") (pintype "passive"))
    )
    (net (code "40") (name "Net-(IC18-EECS)") (class "Default")
      (node (ref "IC18") (pin "1") (pinfunction "EECS_1") (pintype "bidirectional"))
      (node (ref "IC21") (pin "1") (pinfunction "S_1") (pintype "input"))
      (node (ref "R204") (pin "1") (pinfunction "1_1") (pintype "passive"))
    )
    (net (code "41") (name "Net-(IC18-EEDATA)") (class "Default")
      (node (ref "IC18") (pin "55") (pinfunction "EEDATA_55") (pintype "bidirectional"))
      (node (ref "IC21") (pin "3") (pinfunction "D_3") (pintype "input"))
      (node (ref "R205") (pin "2") (pinfunction "2_2") (pintype "passive"))
    )
    (net (code "42") (name "Net-(IC18-OSCI)") (class "Default")
      (node (ref "C207") (pin "2") (pinfunction "2_2") (pintype "passive"))
      (node (ref "IC18") (pin "3") (pinfunction "OSCI_3") (pintype "input"))
      (node (ref "Q2") (pin "1") (pinfunction "X_1") (pintype "passive"))
      (node (ref "TP15") (pin "1") (pinfunction "1_1") (pintype "bidirectional"))
    )
    (net (code "43") (name "Net-(IC18-OSCO)") (class "Default")
      (node (ref "C208") (pin "2") (pinfunction "2_2") (pintype "passive"))
      (node (ref "IC18") (pin "4") (pinfunction "OSCO_4") (pintype "output"))
      (node (ref "Q2") (pin "3") (pinfunction "X_3") (pintype "passive"))
    )
    (net (code "44") (name "Net-(IC18-REF)") (class "Default")
      (node (ref "IC18") (pin "6") (pinfunction "REF_6") (pintype "input"))
      (node (ref "R199") (pin "2") (pinfunction "2_2") (pintype "passive"))
    )
    (net (code "45") (name "Net-(IC18-VPHY)") (class "Default")
      (node (ref "C209") (pin "2") (pinfunction "2_2") (pintype "passive"))
      (node (ref "C210") (pin "2") (pinfunction "2_2") (pintype "passive"))
      (node (ref "IC18") (pin "5") (pinfunction "VPHY_5") (pintype "power_in"))
      (node (ref "L24") (pin "2") (pinfunction "2_2") (pintype "passive"))
    )
    (net (code "46") (name "Net-(IC18-VPLL)") (class "Default")
      (node (ref "C211") (pin "2") (pinfunction "2_2") (pintype "passive"))
      (node (ref "C212") (pin "2") (pinfunction "2_2") (pintype "passive"))
      (node (ref "IC18") (pin "9") (pinfunction "VPLL_9") (pintype "power_in"))
      (node (ref "L25") (pin "2") (pinfunction "2_2") (pintype "passive"))
    )
    (net (code "47") (name "Net-(IC21-Q)") (class "Default")
      (node (ref "IC21") (pin "4") (pinfunction "Q_4") (pintype "output"))
      (node (ref "R202") (pin "1") (pinfunction "1_1") (pintype "passive"))
      (node (ref "R205") (pin "1") (pinfunction "1_1") (pintype "passive"))
    )
    (net (code "48") (name "P1V8_USB") (class "Default")
      (node (ref "C206") (pin "2") (pinfunction "2_2") (pintype "passive"))
      (node (ref "IC18") (pin "2") (pinfunction "VCORE_2") (pintype "power_in"))
      (node (ref "IC18") (pin "31") (pinfunction "VCORE_31") (pintype "power_in"))
      (node (ref "IC18") (pin "43") (pinfunction "VREGOUT_43") (pintype "output"))
    )
    (net (code "49") (name "P2V5") (class "Default")
      (node (ref "C216") (pin "2") (pinfunction "2_2") (pintype "passive"))
      (node (ref "C217") (pin "2") (pinfunction "2_2") (pintype "passive"))
      (node (ref "C218") (pin "2") (pinfunction "2_2") (pintype "passive"))
      (node (ref "IC17") (pin "6") (pinfunction "VCCB_6") (pintype "power_in"))
      (node (ref "IC19") (pin "6") (pinfunction "VCCB_6") (pintype "power_in"))
      (node (ref "IC20") (pin "6") (pinfunction "VCCB_6") (pintype "power_in"))
      (node (ref "R209") (pin "2") (pinfunction "2_2") (pintype "passive"))
    )
    (net (code "50") (name "P3V3") (class "Default")
      (node (ref "C203") (pin "2") (pinfunction "2_2") (pintype "passive"))
      (node (ref "C220") (pin "2") (pinfunction "2_2") (pintype "passive"))
      (node (ref "IC10") (pin "6") (pinfunction "VCCB_6") (pintype "power_in"))
      (node (ref "IC22") (pin "8") (pinfunction "VCCB_8") (pintype "power_in"))
    )
    (net (code "51") (name "P3V3_USB") (class "Default")
      (node (ref "C204") (pin "2") (pinfunction "2_2") (pintype "passive"))
      (node (ref "C205") (pin "2") (pinfunction "2_2") (pintype "passive"))
      (node (ref "C213") (pin "2") (pinfunction "2_2") (pintype "passive"))
      (node (ref "C214") (pin "2") (pinfunction "2_2") (pintype "passive"))
      (node (ref "C215") (pin "2") (pinfunction "2_2") (pintype "passive"))
      (node (ref "C219") (pin "2") (pinfunction "2_2") (pintype "passive"))
      (node (ref "C221") (pin "2") (pinfunction "2_2") (pintype "passive"))
      (node (ref "C222") (pin "2") (pinfunction "2_2") (pintype "passive"))
      (node (ref "C223") (pin "2") (pinfunction "2_2") (pintype "passive"))
      (node (ref "C224") (pin "2") (pinfunction "2_2") (pintype "passive"))
      (node (ref "C227") (pin "2") (pinfunction "2_2") (pintype "passive"))
      (node (ref "IC10") (pin "1") (pinfunction "DIR2_1") (pintype "input"))
      (node (ref "IC10") (pin "10") (pinfunction "DIR1_10") (pintype "input"))
      (node (ref "IC10") (pin "7") (pinfunction "VCCA_7") (pintype "power_in"))
      (node (ref "IC17") (pin "1") (pinfunction "DIR2_1") (pintype "input"))
      (node (ref "IC17") (pin "10") (pinfunction "DIR1_10") (pintype "input"))
      (node (ref "IC17") (pin "7") (pinfunction "VCCA_7") (pintype "power_in"))
      (node (ref "IC18") (pin "16") (pinfunction "VCCIO_16") (pintype "power_in"))
      (node (ref "IC18") (pin "36") (pinfunction "VCCIO_36") (pintype "power_in"))
      (node (ref "IC18") (pin "44") (pinfunction "VREGIN_44") (pintype "input"))
      (node (ref "IC18") (pin "50") (pinfunction "VCCIO_50") (pintype "power_in"))
      (node (ref "IC19") (pin "10") (pinfunction "DIR1_10") (pintype "input"))
      (node (ref "IC19") (pin "7") (pinfunction "VCCA_7") (pintype "power_in"))
      (node (ref "IC20") (pin "1") (pinfunction "DIR2_1") (pintype "input"))
      (node (ref "IC20") (pin "7") (pinfunction "VCCA_7") (pintype "power_in"))
      (node (ref "IC21") (pin "6") (pinfunction "ORG_6") (pintype "input"))
      (node (ref "IC21") (pin "8") (pinfunction "VCC_8") (pintype "power_in"))
      (node (ref "IC22") (pin "1") (pinfunction "VCCA_1") (pintype "power_in"))
      (node (ref "J24") (pin "9") (pinfunction "9_9") (pintype "bidirectional"))
      (node (ref "L23") (pin "2") (pinfunction "2_2") (pintype "passive"))
      (node (ref "L24") (pin "1") (pinfunction "1_1") (pintype "passive"))
      (node (ref "L25") (pin "1") (pinfunction "1_1") (pintype "passive"))
      (node (ref "R192") (pin "2") (pinfunction "2_2") (pintype "passive"))
      (node (ref "R194") (pin "2") (pinfunction "2_2") (pintype "passive"))
      (node (ref "R195") (pin "2") (pinfunction "2_2") (pintype "passive"))
      (node (ref "R196") (pin "2") (pinfunction "2_2") (pintype "passive"))
      (node (ref "R197") (pin "2") (pinfunction "2_2") (pintype "passive"))
      (node (ref "R198") (pin "2") (pinfunction "2_2") (pintype "passive"))
      (node (ref "R202") (pin "2") (pinfunction "2_2") (pintype "passive"))
      (node (ref "R203") (pin "2") (pinfunction "2_2") (pintype "passive"))
      (node (ref "R204") (pin "2") (pinfunction "2_2") (pintype "passive"))
      (node (ref "R206") (pin "2") (pinfunction "2_2") (pintype "passive"))
      (node (ref "R207") (pin "2") (pinfunction "2_2") (pintype "passive"))
      (node (ref "R33") (pin "2") (pinfunction "2_2") (pintype "passive"))
    )
    (net (code "52") (name "unconnected-(IC18-ADBUS4-Pad17)") (class "Default")
      (node (ref "IC18") (pin "17") (pinfunction "ADBUS4_17") (pintype "bidirectional+no_connect"))
    )
    (net (code "53") (name "unconnected-(IC18-ADBUS5-Pad18)") (class "Default")
      (node (ref "IC18") (pin "18") (pinfunction "ADBUS5_18") (pintype "bidirectional+no_connect"))
    )
    (net (code "54") (name "unconnected-(IC18-ADBUS6-Pad19)") (class "Default")
      (node (ref "IC18") (pin "19") (pinfunction "ADBUS6_19") (pintype "bidirectional+no_connect"))
    )
    (net (code "55") (name "unconnected-(IC18-ADBUS7-Pad20)") (class "Default")
      (node (ref "IC18") (pin "20") (pinfunction "ADBUS7_20") (pintype "bidirectional+no_connect"))
    )
    (net (code "56") (name "unconnected-(IC18-BDBUS3-Pad25)") (class "Default")
      (node (ref "IC18") (pin "25") (pinfunction "BDBUS3_25") (pintype "bidirectional+no_connect"))
    )
    (net (code "57") (name "unconnected-(IC18-BDBUS6-Pad28)") (class "Default")
      (node (ref "IC18") (pin "28") (pinfunction "BDBUS6_28") (pintype "bidirectional+no_connect"))
    )
    (net (code "58") (name "unconnected-(IC18-BDBUS7-Pad29)") (class "Default")
      (node (ref "IC18") (pin "29") (pinfunction "BDBUS7_29") (pintype "bidirectional+no_connect"))
    )
    (net (code "59") (name "unconnected-(IC18-CDBUS2-Pad34)") (class "Default")
      (node (ref "IC18") (pin "34") (pinfunction "CDBUS2_34") (pintype "bidirectional+no_connect"))
    )
    (net (code "60") (name "unconnected-(IC18-CDBUS3-Pad35)") (class "Default")
      (node (ref "IC18") (pin "35") (pinfunction "CDBUS3_35") (pintype "bidirectional+no_connect"))
    )
    (net (code "61") (name "unconnected-(IC18-CDBUS4-Pad37)") (class "Default")
      (node (ref "IC18") (pin "37") (pinfunction "CDBUS4_37") (pintype "bidirectional"))
    )
    (net (code "62") (name "unconnected-(IC18-CDBUS5-Pad38)") (class "Default")
      (node (ref "IC18") (pin "38") (pinfunction "CDBUS5_38") (pintype "bidirectional+no_connect"))
    )
    (net (code "63") (name "unconnected-(IC18-CDBUS6-Pad39)") (class "Default")
      (node (ref "IC18") (pin "39") (pinfunction "CDBUS6_39") (pintype "bidirectional+no_connect"))
    )
    (net (code "64") (name "unconnected-(IC18-CDBUS7-Pad40)") (class "Default")
      (node (ref "IC18") (pin "40") (pinfunction "CDBUS7_40") (pintype "bidirectional+no_connect"))
    )
    (net (code "65") (name "unconnected-(IC18-~{PWREN}-Pad54)") (class "Default")
      (node (ref "IC18") (pin "54") (pinfunction "~{PWREN}_54") (pintype "output+no_connect"))
    )
    (net (code "66") (name "unconnected-(IC18-~{SUSPEND}-Pad30)") (class "Default")
      (node (ref "IC18") (pin "30") (pinfunction "~{SUSPEND}_30") (pintype "output+no_connect"))
    )
    (net (code "67") (name "unconnected-(IC21-DU-Pad7)") (class "Default")
      (node (ref "IC21") (pin "7") (pinfunction "DU_7") (pintype "passive+no_connect"))
    )
    (net (code "68") (name "unconnected-(J23-ID-Pad4)") (class "Default")
      (node (ref "J23") (pin "4") (pinfunction "ID_4") (pintype "passive+no_connect"))
    )
  )
)
